# Driver.net
KiCad netlist of a schematic drawn in Altium Designer
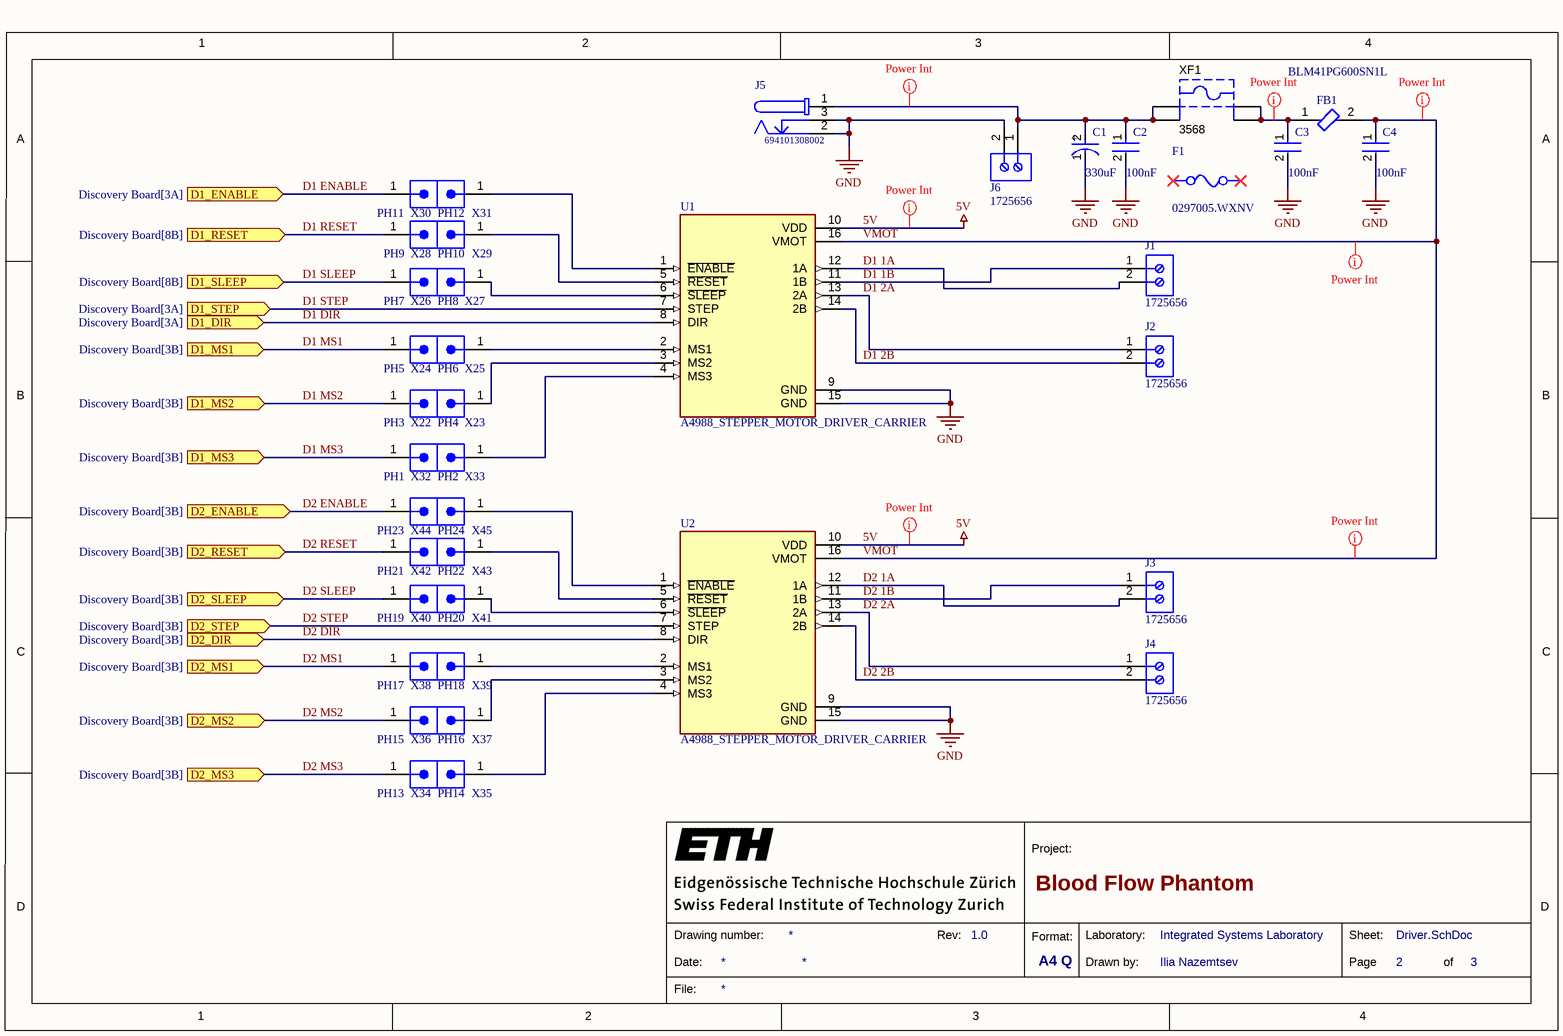
[diagram p0: Driver.SchDoc]

(export (version "E")
  (design (tool "Eeschema 10.0.6"))
  (components
    (comp (ref "C1")
      (value "330uF")
      (footprint "FP-RAD-TH-D_10_0_5-L_12_5-MFG")
      (description "Aluminum Electrolytic Capacitors (Radial Lead Type) 330uF ±20% 35V")
      (fields (field (name "VOLTAGE") "35V") (field (name "TOLERANCE") "20%"))
      (libsource (lib "Altium Content Vault") (part "203bc49f2ac43e59fd269a8c329ed05"))
    )
    (comp (ref "C2")
      (value "100nF")
      (footprint "FP-CL31-IPC_C")
      (description "Cap Ceramic 100nF 50V X7R ±10% SMD 1206 +125°C Embossed T/R")
      (fields (field (name "VOLTAGE") "50V") (field (name "TOLERANCE") "10%"))
      (libsource (lib "Altium Content Vault") (part "b4654b650e69147ec39a6b967a45e02"))
    )
    (comp (ref "C3")
      (value "100nF")
      (footprint "FP-CL31-IPC_C")
      (description "Cap Ceramic 100nF 50V X7R ±10% SMD 1206 +125°C Embossed T/R")
      (fields (field (name "VOLTAGE") "50V") (field (name "TOLERANCE") "10%"))
      (libsource (lib "Altium Content Vault") (part "b4654b650e69147ec39a6b967a45e02"))
    )
    (comp (ref "C4")
      (value "100nF")
      (footprint "FP-CL31-IPC_C")
      (description "Cap Ceramic 100nF 50V X7R ±10% SMD 1206 +125°C Embossed T/R")
      (fields (field (name "VOLTAGE") "50V") (field (name "TOLERANCE") "10%"))
      (libsource (lib "Altium Content Vault") (part "b4654b650e69147ec39a6b967a45e02"))
    )
    (comp (ref "F1")
      (value "0297005.WXNV")
      (footprint "FP-0297-MFG")
      (description "FUSE AUTO 5A 32VDC BLADE MINI")
      (fields
        (field (name "MANUFACTURER") "Littelfuse Inc")
        (field (name "OCTOPART") "https://octopart.com/0297005.wxnv-littelfuse-566870")
      )
      (libsource (lib "Altium Content Vault") (part "375d75c1fe5e4df43ffdd1e3c111aba"))
    )
    (comp (ref "FB1")
      (value "BLM41PG600SN1L")
      (footprint "FP-BLM41-0_2-IPC_B")
      (description "Ferrite Bead, 1806, 60Ω @ 100MHz, 0.009Ω, 6A")
      (fields (field (name "TOLERANCE") "25%"))
      (libsource (lib "Altium Content Vault") (part "5f30dd21d616792df468990f7003faa"))
    )
    (comp (ref "J1")
      (value "1725656")
      (footprint "PHOE-1725656-2")
      (description "Male Header, Pitch 2.54 mm, 1 x 2 Position, Height 9 mm, Tail Length 3.5 mm")
      (fields (field (name "MANUFACTURER") "Phoenix Contact"))
      (libsource (lib "Altium Content Vault") (part "CN-1P-F-TB2"))
    )
    (comp (ref "J2")
      (value "1725656")
      (footprint "PHOE-1725656-2")
      (description "Male Header, Pitch 2.54 mm, 1 x 2 Position, Height 9 mm, Tail Length 3.5 mm")
      (fields (field (name "MANUFACTURER") "Phoenix Contact"))
      (libsource (lib "Altium Content Vault") (part "CN-1P-F-TB2"))
    )
    (comp (ref "J3")
      (value "1725656")
      (footprint "PHOE-1725656-2")
      (description "Male Header, Pitch 2.54 mm, 1 x 2 Position, Height 9 mm, Tail Length 3.5 mm")
      (fields (field (name "MANUFACTURER") "Phoenix Contact"))
      (libsource (lib "Altium Content Vault") (part "CN-1P-F-TB2"))
    )
    (comp (ref "J4")
      (value "1725656")
      (footprint "PHOE-1725656-2")
      (description "Male Header, Pitch 2.54 mm, 1 x 2 Position, Height 9 mm, Tail Length 3.5 mm")
      (fields (field (name "MANUFACTURER") "Phoenix Contact"))
      (libsource (lib "Altium Content Vault") (part "CN-1P-F-TB2"))
    )
    (comp (ref "J5")
      (value "694101308002")
      (footprint "694101308002")
      (description "DC Power Jack Connector Low Profile WR-DC, Male, Right Angled, THT, 2 A, 12 V")
      (fields (field (name "MANUFACTURER") "Wurth Elektronik") (field (name "PUBLISHER") "WurthElektronik"))
      (libsource (lib "Altium Content Vault") (part "WE-JACK-2CD3-RN"))
    )
    (comp (ref "J6")
      (value "1725656")
      (footprint "PHOE-1725656-2")
      (description "Male Header, Pitch 2.54 mm, 1 x 2 Position, Height 9 mm, Tail Length 3.5 mm")
      (fields (field (name "MANUFACTURER") "Phoenix Contact"))
      (libsource (lib "Altium Content Vault") (part "CN-1P-F-TB2"))
    )
    (comp (ref "U1")
      (value "A4988_STEPPER_MOTOR_DRIVER_CARRIER")
      (footprint "MODULE_A4988_STEPPER_MOTOR_DRIVER_CARRIER")
      (description "Stepper motor controler; IC: A4988; 1A; Uin mot: 8Ã·35V")
      (libsource (lib "A4988_STEPPER_MOTOR_DRIVER_CARRIER") (part "A4988_STEPPER_MOTOR_DRIVER_CARRIER"))
    )
    (comp (ref "U2")
      (value "A4988_STEPPER_MOTOR_DRIVER_CARRIER")
      (footprint "MODULE_A4988_STEPPER_MOTOR_DRIVER_CARRIER")
      (description "Stepper motor controler; IC: A4988; 1A; Uin mot: 8Ã·35V")
      (libsource (lib "A4988_STEPPER_MOTOR_DRIVER_CARRIER") (part "A4988_STEPPER_MOTOR_DRIVER_CARRIER"))
    )
    (comp (ref "X22")
      (value "PH3")
      (footprint "68000-101HLF")
      (description "1 Positions Header, Unshrouded Connector  Through Hole Gold or Gold, GXT™")
      (fields
        (field (name "MANUFACTURER") "Amphenol FCI")
        (field (name "MANUFACTURER PART NUMBER") "68000-101HLF")
      )
      (libsource (lib "ETHZ Vault") (part "CON-1x1-Male"))
    )
    (comp (ref "X23")
      (value "PH4")
      (footprint "68000-101HLF")
      (description "1 Positions Header, Unshrouded Connector  Through Hole Gold or Gold, GXT™")
      (fields
        (field (name "MANUFACTURER") "Amphenol FCI")
        (field (name "MANUFACTURER PART NUMBER") "68000-101HLF")
      )
      (libsource (lib "ETHZ Vault") (part "CON-1x1-Male"))
    )
    (comp (ref "X24")
      (value "PH5")
      (footprint "68000-101HLF")
      (description "1 Positions Header, Unshrouded Connector  Through Hole Gold or Gold, GXT™")
      (fields
        (field (name "MANUFACTURER") "Amphenol FCI")
        (field (name "MANUFACTURER PART NUMBER") "68000-101HLF")
      )
      (libsource (lib "ETHZ Vault") (part "CON-1x1-Male"))
    )
    (comp (ref "X25")
      (value "PH6")
      (footprint "68000-101HLF")
      (description "1 Positions Header, Unshrouded Connector  Through Hole Gold or Gold, GXT™")
      (fields
        (field (name "MANUFACTURER") "Amphenol FCI")
        (field (name "MANUFACTURER PART NUMBER") "68000-101HLF")
      )
      (libsource (lib "ETHZ Vault") (part "CON-1x1-Male"))
    )
    (comp (ref "X26")
      (value "PH7")
      (footprint "68000-101HLF")
      (description "1 Positions Header, Unshrouded Connector  Through Hole Gold or Gold, GXT™")
      (fields
        (field (name "MANUFACTURER") "Amphenol FCI")
        (field (name "MANUFACTURER PART NUMBER") "68000-101HLF")
      )
      (libsource (lib "ETHZ Vault") (part "CON-1x1-Male"))
    )
    (comp (ref "X27")
      (value "PH8")
      (footprint "68000-101HLF")
      (description "1 Positions Header, Unshrouded Connector  Through Hole Gold or Gold, GXT™")
      (fields
        (field (name "MANUFACTURER") "Amphenol FCI")
        (field (name "MANUFACTURER PART NUMBER") "68000-101HLF")
      )
      (libsource (lib "ETHZ Vault") (part "CON-1x1-Male"))
    )
    (comp (ref "X28")
      (value "PH9")
      (footprint "68000-101HLF")
      (description "1 Positions Header, Unshrouded Connector  Through Hole Gold or Gold, GXT™")
      (fields
        (field (name "MANUFACTURER") "Amphenol FCI")
        (field (name "MANUFACTURER PART NUMBER") "68000-101HLF")
      )
      (libsource (lib "ETHZ Vault") (part "CON-1x1-Male"))
    )
    (comp (ref "X29")
      (value "PH10")
      (footprint "68000-101HLF")
      (description "1 Positions Header, Unshrouded Connector  Through Hole Gold or Gold, GXT™")
      (fields
        (field (name "MANUFACTURER") "Amphenol FCI")
        (field (name "MANUFACTURER PART NUMBER") "68000-101HLF")
      )
      (libsource (lib "ETHZ Vault") (part "CON-1x1-Male"))
    )
    (comp (ref "X30")
      (value "PH11")
      (footprint "68000-101HLF")
      (description "1 Positions Header, Unshrouded Connector  Through Hole Gold or Gold, GXT™")
      (fields
        (field (name "MANUFACTURER") "Amphenol FCI")
        (field (name "MANUFACTURER PART NUMBER") "68000-101HLF")
      )
      (libsource (lib "ETHZ Vault") (part "CON-1x1-Male"))
    )
    (comp (ref "X31")
      (value "PH12")
      (footprint "68000-101HLF")
      (description "1 Positions Header, Unshrouded Connector  Through Hole Gold or Gold, GXT™")
      (fields
        (field (name "MANUFACTURER") "Amphenol FCI")
        (field (name "MANUFACTURER PART NUMBER") "68000-101HLF")
      )
      (libsource (lib "ETHZ Vault") (part "CON-1x1-Male"))
    )
    (comp (ref "X32")
      (value "PH1")
      (footprint "68000-101HLF")
      (description "1 Positions Header, Unshrouded Connector  Through Hole Gold or Gold, GXT™")
      (fields
        (field (name "MANUFACTURER") "Amphenol FCI")
        (field (name "MANUFACTURER PART NUMBER") "68000-101HLF")
      )
      (libsource (lib "ETHZ Vault") (part "CON-1x1-Male"))
    )
    (comp (ref "X33")
      (value "PH2")
      (footprint "68000-101HLF")
      (description "1 Positions Header, Unshrouded Connector  Through Hole Gold or Gold, GXT™")
      (fields
        (field (name "MANUFACTURER") "Amphenol FCI")
        (field (name "MANUFACTURER PART NUMBER") "68000-101HLF")
      )
      (libsource (lib "ETHZ Vault") (part "CON-1x1-Male"))
    )
    (comp (ref "X34")
      (value "PH13")
      (footprint "68000-101HLF")
      (description "1 Positions Header, Unshrouded Connector  Through Hole Gold or Gold, GXT™")
      (fields
        (field (name "MANUFACTURER") "Amphenol FCI")
        (field (name "MANUFACTURER PART NUMBER") "68000-101HLF")
      )
      (libsource (lib "ETHZ Vault") (part "CON-1x1-Male"))
    )
    (comp (ref "X35")
      (value "PH14")
      (footprint "68000-101HLF")
      (description "1 Positions Header, Unshrouded Connector  Through Hole Gold or Gold, GXT™")
      (fields
        (field (name "MANUFACTURER") "Amphenol FCI")
        (field (name "MANUFACTURER PART NUMBER") "68000-101HLF")
      )
      (libsource (lib "ETHZ Vault") (part "CON-1x1-Male"))
    )
    (comp (ref "X36")
      (value "PH15")
      (footprint "68000-101HLF")
      (description "1 Positions Header, Unshrouded Connector  Through Hole Gold or Gold, GXT™")
      (fields
        (field (name "MANUFACTURER") "Amphenol FCI")
        (field (name "MANUFACTURER PART NUMBER") "68000-101HLF")
      )
      (libsource (lib "ETHZ Vault") (part "CON-1x1-Male"))
    )
    (comp (ref "X37")
      (value "PH16")
      (footprint "68000-101HLF")
      (description "1 Positions Header, Unshrouded Connector  Through Hole Gold or Gold, GXT™")
      (fields
        (field (name "MANUFACTURER") "Amphenol FCI")
        (field (name "MANUFACTURER PART NUMBER") "68000-101HLF")
      )
      (libsource (lib "ETHZ Vault") (part "CON-1x1-Male"))
    )
    (comp (ref "X38")
      (value "PH17")
      (footprint "68000-101HLF")
      (description "1 Positions Header, Unshrouded Connector  Through Hole Gold or Gold, GXT™")
      (fields
        (field (name "MANUFACTURER") "Amphenol FCI")
        (field (name "MANUFACTURER PART NUMBER") "68000-101HLF")
      )
      (libsource (lib "ETHZ Vault") (part "CON-1x1-Male"))
    )
    (comp (ref "X39")
      (value "PH18")
      (footprint "68000-101HLF")
      (description "1 Positions Header, Unshrouded Connector  Through Hole Gold or Gold, GXT™")
      (fields
        (field (name "MANUFACTURER") "Amphenol FCI")
        (field (name "MANUFACTURER PART NUMBER") "68000-101HLF")
      )
      (libsource (lib "ETHZ Vault") (part "CON-1x1-Male"))
    )
    (comp (ref "X40")
      (value "PH19")
      (footprint "68000-101HLF")
      (description "1 Positions Header, Unshrouded Connector  Through Hole Gold or Gold, GXT™")
      (fields
        (field (name "MANUFACTURER") "Amphenol FCI")
        (field (name "MANUFACTURER PART NUMBER") "68000-101HLF")
      )
      (libsource (lib "ETHZ Vault") (part "CON-1x1-Male"))
    )
    (comp (ref "X41")
      (value "PH20")
      (footprint "68000-101HLF")
      (description "1 Positions Header, Unshrouded Connector  Through Hole Gold or Gold, GXT™")
      (fields
        (field (name "MANUFACTURER") "Amphenol FCI")
        (field (name "MANUFACTURER PART NUMBER") "68000-101HLF")
      )
      (libsource (lib "ETHZ Vault") (part "CON-1x1-Male"))
    )
    (comp (ref "X42")
      (value "PH21")
      (footprint "68000-101HLF")
      (description "1 Positions Header, Unshrouded Connector  Through Hole Gold or Gold, GXT™")
      (fields
        (field (name "MANUFACTURER") "Amphenol FCI")
        (field (name "MANUFACTURER PART NUMBER") "68000-101HLF")
      )
      (libsource (lib "ETHZ Vault") (part "CON-1x1-Male"))
    )
    (comp (ref "X43")
      (value "PH22")
      (footprint "68000-101HLF")
      (description "1 Positions Header, Unshrouded Connector  Through Hole Gold or Gold, GXT™")
      (fields
        (field (name "MANUFACTURER") "Amphenol FCI")
        (field (name "MANUFACTURER PART NUMBER") "68000-101HLF")
      )
      (libsource (lib "ETHZ Vault") (part "CON-1x1-Male"))
    )
    (comp (ref "X44")
      (value "PH23")
      (footprint "68000-101HLF")
      (description "1 Positions Header, Unshrouded Connector  Through Hole Gold or Gold, GXT™")
      (fields
        (field (name "MANUFACTURER") "Amphenol FCI")
        (field (name "MANUFACTURER PART NUMBER") "68000-101HLF")
      )
      (libsource (lib "ETHZ Vault") (part "CON-1x1-Male"))
    )
    (comp (ref "X45")
      (value "PH24")
      (footprint "68000-101HLF")
      (description "1 Positions Header, Unshrouded Connector  Through Hole Gold or Gold, GXT™")
      (fields
        (field (name "MANUFACTURER") "Amphenol FCI")
        (field (name "MANUFACTURER PART NUMBER") "68000-101HLF")
      )
      (libsource (lib "ETHZ Vault") (part "CON-1x1-Male"))
    )
    (comp (ref "XF1")
      (value "3568")
      (footprint "KSTN-3568_V")
      (description "Fuse Holder, 20 A, 500 V, -50 to 145 degC, 4-Pin THD, RoHS")
      (fields (field (name "MANUFACTURER") "Keystone"))
      (libsource (lib "Altium Content Vault") (part "FUSE_HOLDER-4"))
    )
  )
  (nets
    (net (code "1") (name "/D1 1A") (class "Default")
      (node (ref "J1") (pin "2") (pinfunction "2_2") (pintype "passive"))
      (node (ref "U1") (pin "12") (pinfunction "1A_12") (pintype "output"))
    )
    (net (code "2") (name "/D1 1B") (class "Default")
      (node (ref "J1") (pin "1") (pinfunction "1_1") (pintype "passive"))
      (node (ref "U1") (pin "11") (pinfunction "1B_11") (pintype "output"))
    )
    (net (code "3") (name "/D1 2A") (class "Default")
      (node (ref "J2") (pin "1") (pinfunction "1_1") (pintype "passive"))
      (node (ref "U1") (pin "13") (pinfunction "2A_13") (pintype "output"))
    )
    (net (code "4") (name "/D1 2B") (class "Default")
      (node (ref "J2") (pin "2") (pinfunction "2_2") (pintype "passive"))
      (node (ref "U1") (pin "14") (pinfunction "2B_14") (pintype "output"))
    )
    (net (code "5") (name "/D1 DIR") (class "Default")
      (node (ref "U1") (pin "8") (pinfunction "DIR_8") (pintype "input"))
    )
    (net (code "6") (name "/D1 ENABLE") (class "Default")
      (node (ref "X30") (pin "1") (pinfunction "1_1") (pintype "passive"))
    )
    (net (code "7") (name "/D1 MS1") (class "Default")
      (node (ref "X24") (pin "1") (pinfunction "1_1") (pintype "passive"))
    )
    (net (code "8") (name "/D1 MS2") (class "Default")
      (node (ref "X22") (pin "1") (pinfunction "1_1") (pintype "passive"))
    )
    (net (code "9") (name "/D1 MS3") (class "Default")
      (node (ref "X32") (pin "1") (pinfunction "1_1") (pintype "passive"))
    )
    (net (code "10") (name "/D1 RESET") (class "Default")
      (node (ref "X28") (pin "1") (pinfunction "1_1") (pintype "passive"))
    )
    (net (code "11") (name "/D1 SLEEP") (class "Default")
      (node (ref "X26") (pin "1") (pinfunction "1_1") (pintype "passive"))
    )
    (net (code "12") (name "/D1 STEP") (class "Default")
      (node (ref "U1") (pin "7") (pinfunction "STEP_7") (pintype "input"))
    )
    (net (code "13") (name "/D2 1A") (class "Default")
      (node (ref "J3") (pin "2") (pinfunction "2_2") (pintype "passive"))
      (node (ref "U2") (pin "12") (pinfunction "1A_12") (pintype "output"))
    )
    (net (code "14") (name "/D2 1B") (class "Default")
      (node (ref "J3") (pin "1") (pinfunction "1_1") (pintype "passive"))
      (node (ref "U2") (pin "11") (pinfunction "1B_11") (pintype "output"))
    )
    (net (code "15") (name "/D2 2A") (class "Default")
      (node (ref "J4") (pin "1") (pinfunction "1_1") (pintype "passive"))
      (node (ref "U2") (pin "13") (pinfunction "2A_13") (pintype "output"))
    )
    (net (code "16") (name "/D2 2B") (class "Default")
      (node (ref "J4") (pin "2") (pinfunction "2_2") (pintype "passive"))
      (node (ref "U2") (pin "14") (pinfunction "2B_14") (pintype "output"))
    )
    (net (code "17") (name "/D2 DIR") (class "Default")
      (node (ref "U2") (pin "8") (pinfunction "DIR_8") (pintype "input"))
    )
    (net (code "18") (name "/D2 ENABLE") (class "Default")
      (node (ref "X44") (pin "1") (pinfunction "1_1") (pintype "passive"))
    )
    (net (code "19") (name "/D2 MS1") (class "Default")
      (node (ref "X38") (pin "1") (pinfunction "1_1") (pintype "passive"))
    )
    (net (code "20") (name "/D2 MS2") (class "Default")
      (node (ref "X36") (pin "1") (pinfunction "1_1") (pintype "passive"))
    )
    (net (code "21") (name "/D2 MS3") (class "Default")
      (node (ref "X34") (pin "1") (pinfunction "1_1") (pintype "passive"))
    )
    (net (code "22") (name "/D2 RESET") (class "Default")
      (node (ref "X42") (pin "1") (pinfunction "1_1") (pintype "passive"))
    )
    (net (code "23") (name "/D2 SLEEP") (class "Default")
      (node (ref "X40") (pin "1") (pinfunction "1_1") (pintype "passive"))
    )
    (net (code "24") (name "/D2 STEP") (class "Default")
      (node (ref "U2") (pin "7") (pinfunction "STEP_7") (pintype "input"))
    )
    (net (code "25") (name "/VMOT") (class "Default")
      (node (ref "C4") (pin "1") (pinfunction "1_1") (pintype "passive"))
      (node (ref "FB1") (pin "2") (pinfunction "2_2") (pintype "passive"))
      (node (ref "U1") (pin "16") (pinfunction "VMOT_16") (pintype "power_in"))
      (node (ref "U2") (pin "16") (pinfunction "VMOT_16") (pintype "power_in"))
    )
    (net (code "26") (name "5V") (class "Default")
      (node (ref "U1") (pin "10") (pinfunction "VDD_10") (pintype "power_in"))
      (node (ref "U2") (pin "10") (pinfunction "VDD_10") (pintype "power_in"))
    )
    (net (code "27") (name "GND") (class "Default")
      (node (ref "C1") (pin "1") (pinfunction "C_1") (pintype "passive"))
      (node (ref "C2") (pin "2") (pinfunction "2_2") (pintype "passive"))
      (node (ref "C3") (pin "2") (pinfunction "2_2") (pintype "passive"))
      (node (ref "C4") (pin "2") (pinfunction "2_2") (pintype "passive"))
      (node (ref "J5") (pin "2") (pinfunction "2_2") (pintype "passive"))
      (node (ref "J5") (pin "3") (pinfunction "3_3") (pintype "passive"))
      (node (ref "J6") (pin "2") (pinfunction "2_2") (pintype "passive"))
      (node (ref "U1") (pin "15") (pinfunction "GND_15") (pintype "power_in"))
      (node (ref "U1") (pin "9") (pinfunction "GND_9") (pintype "power_in"))
      (node (ref "U2") (pin "15") (pinfunction "GND_15") (pintype "power_in"))
      (node (ref "U2") (pin "9") (pinfunction "GND_9") (pintype "power_in"))
    )
    (net (code "28") (name "Net-(C1-A)") (class "Default")
      (node (ref "C1") (pin "2") (pinfunction "A_2") (pintype "passive"))
      (node (ref "C2") (pin "1") (pinfunction "1_1") (pintype "passive"))
      (node (ref "J5") (pin "1") (pinfunction "1_1") (pintype "passive"))
      (node (ref "J6") (pin "1") (pinfunction "1_1") (pintype "passive"))
      (node (ref "XF1") (pin "1") (pinfunction "1_1") (pintype "passive"))
      (node (ref "XF1") (pin "2") (pinfunction "2_2") (pintype "passive"))
    )
    (net (code "29") (name "Net-(C3-Pad1)") (class "Default")
      (node (ref "C3") (pin "1") (pinfunction "1_1") (pintype "passive"))
      (node (ref "FB1") (pin "1") (pinfunction "1_1") (pintype "passive"))
      (node (ref "XF1") (pin "3") (pinfunction "3_3") (pintype "passive"))
      (node (ref "XF1") (pin "4") (pinfunction "4_4") (pintype "passive"))
    )
    (net (code "30") (name "Net-(U1-MS1)") (class "Default")
      (node (ref "U1") (pin "2") (pinfunction "MS1_2") (pintype "input"))
      (node (ref "X25") (pin "1") (pinfunction "1_1") (pintype "passive"))
    )
    (net (code "31") (name "Net-(U1-MS2)") (class "Default")
      (node (ref "U1") (pin "3") (pinfunction "MS2_3") (pintype "input"))
      (node (ref "X23") (pin "1") (pinfunction "1_1") (pintype "passive"))
    )
    (net (code "32") (name "Net-(U1-MS3)") (class "Default")
      (node (ref "U1") (pin "4") (pinfunction "MS3_4") (pintype "input"))
      (node (ref "X33") (pin "1") (pinfunction "1_1") (pintype "passive"))
    )
    (net (code "33") (name "Net-(U1-~{ENABLE})") (class "Default")
      (node (ref "U1") (pin "1") (pinfunction "~{ENABLE}_1") (pintype "input"))
      (node (ref "X31") (pin "1") (pinfunction "1_1") (pintype "passive"))
    )
    (net (code "34") (name "Net-(U1-~{RESET})") (class "Default")
      (node (ref "U1") (pin "5") (pinfunction "~{RESET}_5") (pintype "input"))
      (node (ref "X29") (pin "1") (pinfunction "1_1") (pintype "passive"))
    )
    (net (code "35") (name "Net-(U1-~{SLEEP})") (class "Default")
      (node (ref "U1") (pin "6") (pinfunction "~{SLEEP}_6") (pintype "input"))
      (node (ref "X27") (pin "1") (pinfunction "1_1") (pintype "passive"))
    )
    (net (code "36") (name "Net-(U2-MS1)") (class "Default")
      (node (ref "U2") (pin "2") (pinfunction "MS1_2") (pintype "input"))
      (node (ref "X39") (pin "1") (pinfunction "1_1") (pintype "passive"))
    )
    (net (code "37") (name "Net-(U2-MS2)") (class "Default")
      (node (ref "U2") (pin "3") (pinfunction "MS2_3") (pintype "input"))
      (node (ref "X37") (pin "1") (pinfunction "1_1") (pintype "passive"))
    )
    (net (code "38") (name "Net-(U2-MS3)") (class "Default")
      (node (ref "U2") (pin "4") (pinfunction "MS3_4") (pintype "input"))
      (node (ref "X35") (pin "1") (pinfunction "1_1") (pintype "passive"))
    )
    (net (code "39") (name "Net-(U2-~{ENABLE})") (class "Default")
      (node (ref "U2") (pin "1") (pinfunction "~{ENABLE}_1") (pintype "input"))
      (node (ref "X45") (pin "1") (pinfunction "1_1") (pintype "passive"))
    )
    (net (code "40") (name "Net-(U2-~{RESET})") (class "Default")
      (node (ref "U2") (pin "5") (pinfunction "~{RESET}_5") (pintype "input"))
      (node (ref "X43") (pin "1") (pinfunction "1_1") (pintype "passive"))
    )
    (net (code "41") (name "Net-(U2-~{SLEEP})") (class "Default")
      (node (ref "U2") (pin "6") (pinfunction "~{SLEEP}_6") (pintype "input"))
      (node (ref "X41") (pin "1") (pinfunction "1_1") (pintype "passive"))
    )
  )
)
